# Integrated_LED.net
KiCad netlist of a schematic drawn in Altium Designer
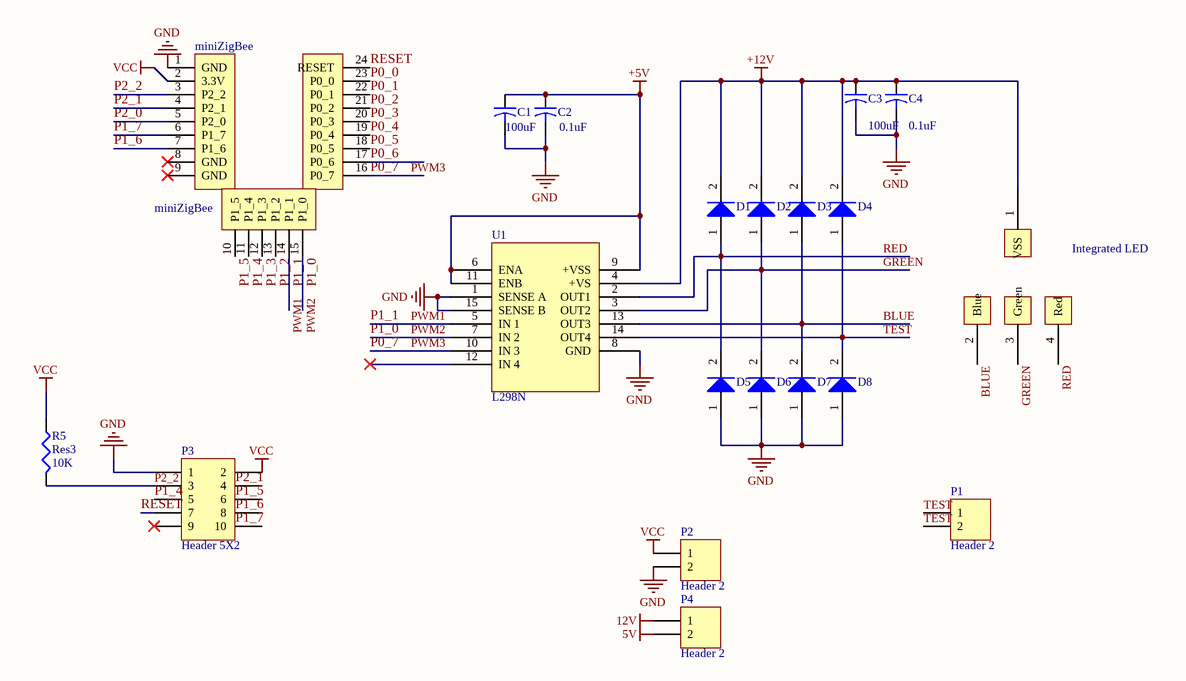
[diagram p0: Integrated LED.SCHDOC]

(export (version "E")
  (design (tool "Eeschema 10.0.6"))
  (components
    (comp (ref "C1")
      (value "100uF")
      (footprint "PCBComponent_1")
      (description "Capacitor")
      (fields (field (name "PUBLISHER") "Altium Limited"))
      (libsource (lib "Miscellaneous Devices") (part "Cap2"))
    )
    (comp (ref "C2")
      (value "0.1uF")
      (footprint "PCBComponent_1")
      (description "Capacitor")
      (fields (field (name "PUBLISHER") "Altium Limited"))
      (libsource (lib "Miscellaneous Devices") (part "Cap2"))
    )
    (comp (ref "C3")
      (value "100uF")
      (footprint "PCBComponent_1")
      (description "Capacitor")
      (fields (field (name "PUBLISHER") "Altium Limited"))
      (libsource (lib "Miscellaneous Devices") (part "Cap2"))
    )
    (comp (ref "C4")
      (value "0.1uF")
      (footprint "PCBComponent_1")
      (description "Capacitor")
      (fields (field (name "PUBLISHER") "Altium Limited"))
      (libsource (lib "Miscellaneous Devices") (part "Cap2"))
    )
    (comp (ref "D1")
      (value "IN4007")
      (footprint "IN4007")
      (libsource (lib "my Integrated lib ") (part "IN4007"))
    )
    (comp (ref "D2")
      (value "IN4007")
      (footprint "IN4007")
      (libsource (lib "my Integrated lib ") (part "IN4007"))
    )
    (comp (ref "D3")
      (value "IN4007")
      (footprint "IN4007")
      (libsource (lib "my Integrated lib ") (part "IN4007"))
    )
    (comp (ref "D4")
      (value "IN4007")
      (footprint "IN4007")
      (libsource (lib "my Integrated lib ") (part "IN4007"))
    )
    (comp (ref "D5")
      (value "IN4007")
      (footprint "IN4007")
      (libsource (lib "my Integrated lib ") (part "IN4007"))
    )
    (comp (ref "D6")
      (value "IN4007")
      (footprint "IN4007")
      (libsource (lib "my Integrated lib ") (part "IN4007"))
    )
    (comp (ref "D7")
      (value "IN4007")
      (footprint "IN4007")
      (libsource (lib "my Integrated lib ") (part "IN4007"))
    )
    (comp (ref "D8")
      (value "IN4007")
      (footprint "IN4007")
      (libsource (lib "my Integrated lib ") (part "IN4007"))
    )
    (comp (ref "Integrated LED")
      (value "Integrated LED")
      (footprint "Integrated LED")
      (libsource (lib "my Integrated lib ") (part "Integrated LED"))
    )
    (comp (ref "miniZigBee")
      (value "miniZigBee")
      (footprint "miniZigBee")
      (libsource (lib "my Integrated lib ") (part "miniZigBee"))
    )
    (comp (ref "P1")
      (value "Header 2")
      (footprint "HDR1X2")
      (description "Header, 2-Pin")
      (fields (field (name "PUBLISHER") "Altium Limited"))
      (libsource (lib "Miscellaneous Connectors") (part "Header 2"))
    )
    (comp (ref "P2")
      (value "Header 2")
      (footprint "HDR1X2")
      (description "Header, 2-Pin")
      (fields (field (name "PUBLISHER") "Altium Limited"))
      (libsource (lib "Miscellaneous Connectors") (part "Header 2"))
    )
    (comp (ref "P3")
      (value "Header 5X2")
      (footprint "HDR2X5")
      (description "Header, 5-Pin, Dual row")
      (fields (field (name "PUBLISHER") "Altium Limited"))
      (libsource (lib "Miscellaneous Connectors") (part "Header 5X2"))
    )
    (comp (ref "P4")
      (value "Header 2")
      (footprint "HDR1X2")
      (description "Header, 2-Pin")
      (fields (field (name "PUBLISHER") "Altium Limited"))
      (libsource (lib "Miscellaneous Connectors") (part "Header 2"))
    )
    (comp (ref "R5")
      (value "Res3")
      (footprint "J1-0603")
      (description "Resistor")
      (fields (field (name "ALTIUM_VALUE") "10K") (field (name "PUBLISHER") "Altium Limited"))
      (libsource (lib "Miscellaneous Devices") (part "Res3"))
    )
    (comp (ref "U1") (value "L298N") (footprint "L298N - duplicate") (libsource (lib "KU1") (part "L298N")))
  )
  (nets
    (net (code "1") (name "+5V") (class "Default")
      (node (ref "C1") (pin "1") (pinfunction "1_1") (pintype "passive"))
      (node (ref "C2") (pin "1") (pinfunction "1_1") (pintype "passive"))
      (node (ref "U1") (pin "11") (pinfunction "ENB_11") (pintype "passive"))
      (node (ref "U1") (pin "6") (pinfunction "ENA_6") (pintype "passive"))
      (node (ref "U1") (pin "9") (pinfunction "+VSS_9") (pintype "passive"))
    )
    (net (code "2") (name "+12V") (class "Default")
      (node (ref "C3") (pin "1") (pinfunction "1_1") (pintype "passive"))
      (node (ref "C4") (pin "1") (pinfunction "1_1") (pintype "passive"))
      (node (ref "D1") (pin "2") (pinfunction "K_2") (pintype "passive"))
      (node (ref "D2") (pin "2") (pinfunction "K_2") (pintype "passive"))
      (node (ref "D3") (pin "2") (pinfunction "K_2") (pintype "passive"))
      (node (ref "D4") (pin "2") (pinfunction "K_2") (pintype "passive"))
      (node (ref "Integrated LED") (pin "1") (pinfunction "VSS_1") (pintype "passive"))
      (node (ref "U1") (pin "4") (pinfunction "+VS_4") (pintype "passive"))
    )
    (net (code "3") (name "/BLUE") (class "Default")
      (node (ref "D3") (pin "1") (pinfunction "A_1") (pintype "passive"))
      (node (ref "D7") (pin "2") (pinfunction "K_2") (pintype "passive"))
      (node (ref "Integrated LED") (pin "2") (pinfunction "Blue_2") (pintype "passive"))
      (node (ref "U1") (pin "13") (pinfunction "OUT3_13") (pintype "passive"))
    )
    (net (code "4") (name "/GREEN") (class "Default")
      (node (ref "D2") (pin "1") (pinfunction "A_1") (pintype "passive"))
      (node (ref "D6") (pin "2") (pinfunction "K_2") (pintype "passive"))
      (node (ref "Integrated LED") (pin "3") (pinfunction "Green_3") (pintype "passive"))
      (node (ref "U1") (pin "3") (pinfunction "OUT2_3") (pintype "passive"))
    )
    (net (code "5") (name "/P0_0") (class "Default")
      (node (ref "miniZigBee") (pin "23") (pinfunction "P0_0_23") (pintype "passive"))
    )
    (net (code "6") (name "/P0_1") (class "Default")
      (node (ref "miniZigBee") (pin "22") (pinfunction "P0_1_22") (pintype "passive"))
    )
    (net (code "7") (name "/P0_2") (class "Default")
      (node (ref "miniZigBee") (pin "21") (pinfunction "P0_2_21") (pintype "passive"))
    )
    (net (code "8") (name "/P0_3") (class "Default")
      (node (ref "miniZigBee") (pin "20") (pinfunction "P0_3_20") (pintype "passive"))
    )
    (net (code "9") (name "/P0_4") (class "Default")
      (node (ref "miniZigBee") (pin "19") (pinfunction "P0_4_19") (pintype "passive"))
    )
    (net (code "10") (name "/P0_5") (class "Default")
      (node (ref "miniZigBee") (pin "18") (pinfunction "P0_5_18") (pintype "passive"))
    )
    (net (code "11") (name "/P0_6") (class "Default")
      (node (ref "miniZigBee") (pin "17") (pinfunction "P0_6_17") (pintype "passive"))
    )
    (net (code "12") (name "/P0_7") (class "Default")
      (node (ref "U1") (pin "10") (pinfunction "IN_3_10") (pintype "passive"))
      (node (ref "miniZigBee") (pin "16") (pinfunction "P0_7_16") (pintype "passive"))
    )
    (net (code "13") (name "/P1_0") (class "Default")
      (node (ref "U1") (pin "7") (pinfunction "IN_2_7") (pintype "passive"))
      (node (ref "miniZigBee") (pin "15") (pinfunction "P1_0_15") (pintype "passive"))
    )
    (net (code "14") (name "/P1_1") (class "Default")
      (node (ref "U1") (pin "5") (pinfunction "IN_1_5") (pintype "passive"))
      (node (ref "miniZigBee") (pin "14") (pinfunction "P1_1_14") (pintype "passive"))
    )
    (net (code "15") (name "/P1_2") (class "Default")
      (node (ref "miniZigBee") (pin "13") (pinfunction "P1_2_13") (pintype "passive"))
    )
    (net (code "16") (name "/P1_3") (class "Default")
      (node (ref "miniZigBee") (pin "12") (pinfunction "P1_3_12") (pintype "passive"))
    )
    (net (code "17") (name "/P1_4") (class "Default")
      (node (ref "P3") (pin "5") (pinfunction "5_5") (pintype "passive"))
      (node (ref "miniZigBee") (pin "11") (pinfunction "P1_4_11") (pintype "passive"))
    )
    (net (code "18") (name "/P1_5") (class "Default")
      (node (ref "miniZigBee") (pin "10") (pinfunction "P1_5_10") (pintype "passive"))
    )
    (net (code "19") (name "/P1_6") (class "Default")
      (node (ref "miniZigBee") (pin "7") (pinfunction "P1_6_7") (pintype "passive"))
    )
    (net (code "20") (name "/P1_7") (class "Default")
      (node (ref "miniZigBee") (pin "6") (pinfunction "P1_7_6") (pintype "passive"))
    )
    (net (code "21") (name "/P2_0") (class "Default")
      (node (ref "miniZigBee") (pin "5") (pinfunction "P2_0_5") (pintype "passive"))
    )
    (net (code "22") (name "/P2_1") (class "Default")
      (node (ref "miniZigBee") (pin "4") (pinfunction "P2_1_4") (pintype "passive"))
    )
    (net (code "23") (name "/P2_2") (class "Default")
      (node (ref "P3") (pin "3") (pinfunction "3_3") (pintype "passive"))
      (node (ref "R5") (pin "2") (pinfunction "2_2") (pintype "passive"))
      (node (ref "miniZigBee") (pin "3") (pinfunction "P2_2_3") (pintype "passive"))
    )
    (net (code "24") (name "/RED") (class "Default")
      (node (ref "D1") (pin "1") (pinfunction "A_1") (pintype "passive"))
      (node (ref "D5") (pin "2") (pinfunction "K_2") (pintype "passive"))
      (node (ref "Integrated LED") (pin "4") (pinfunction "Red_4") (pintype "passive"))
      (node (ref "U1") (pin "2") (pinfunction "OUT1_2") (pintype "passive"))
    )
    (net (code "25") (name "/RESET") (class "Default")
      (node (ref "P3") (pin "7") (pinfunction "7_7") (pintype "passive"))
      (node (ref "miniZigBee") (pin "24") (pinfunction "RESET_24") (pintype "passive"))
    )
    (net (code "26") (name "/TEST") (class "Default")
      (node (ref "D4") (pin "1") (pinfunction "A_1") (pintype "passive"))
      (node (ref "D8") (pin "2") (pinfunction "K_2") (pintype "passive"))
      (node (ref "P1") (pin "1") (pinfunction "1_1") (pintype "passive"))
      (node (ref "P1") (pin "2") (pinfunction "2_2") (pintype "passive"))
      (node (ref "U1") (pin "14") (pinfunction "OUT4_14") (pintype "passive"))
    )
    (net (code "27") (name "5V") (class "Default")
      (node (ref "P4") (pin "2") (pinfunction "2_2") (pintype "passive"))
    )
    (net (code "28") (name "12V") (class "Default")
      (node (ref "P4") (pin "1") (pinfunction "1_1") (pintype "passive"))
    )
    (net (code "29") (name "GND") (class "Default")
      (node (ref "C1") (pin "2") (pinfunction "2_2") (pintype "passive"))
      (node (ref "C2") (pin "2") (pinfunction "2_2") (pintype "passive"))
      (node (ref "C3") (pin "2") (pinfunction "2_2") (pintype "passive"))
      (node (ref "C4") (pin "2") (pinfunction "2_2") (pintype "passive"))
      (node (ref "D5") (pin "1") (pinfunction "A_1") (pintype "passive"))
      (node (ref "D6") (pin "1") (pinfunction "A_1") (pintype "passive"))
      (node (ref "D7") (pin "1") (pinfunction "A_1") (pintype "passive"))
      (node (ref "D8") (pin "1") (pinfunction "A_1") (pintype "passive"))
      (node (ref "P2") (pin "2") (pinfunction "2_2") (pintype "passive"))
      (node (ref "P3") (pin "1") (pinfunction "1_1") (pintype "passive"))
      (node (ref "U1") (pin "1") (pinfunction "SENSE_A_1") (pintype "passive"))
      (node (ref "U1") (pin "15") (pinfunction "SENSE_B_15") (pintype "passive"))
      (node (ref "U1") (pin "8") (pinfunction "GND_8") (pintype "passive"))
      (node (ref "miniZigBee") (pin "1") (pinfunction "GND_1") (pintype "passive"))
    )
    (net (code "30") (name "VCC") (class "Default")
      (node (ref "P2") (pin "1") (pinfunction "1_1") (pintype "passive"))
      (node (ref "P3") (pin "2") (pinfunction "2_2") (pintype "passive"))
      (node (ref "R5") (pin "1") (pinfunction "1_1") (pintype "passive"))
      (node (ref "miniZigBee") (pin "2") (pinfunction "3.3V_2") (pintype "passive"))
    )
    (net (code "31") (name "unconnected-(P3-Pad4)") (class "Default")
      (node (ref "P3") (pin "4") (pinfunction "4_4") (pintype "passive"))
    )
    (net (code "32") (name "unconnected-(P3-Pad6)") (class "Default")
      (node (ref "P3") (pin "6") (pinfunction "6_6") (pintype "passive"))
    )
    (net (code "33") (name "unconnected-(P3-Pad8)") (class "Default")
      (node (ref "P3") (pin "8") (pinfunction "8_8") (pintype "passive"))
    )
    (net (code "34") (name "unconnected-(P3-Pad9)") (class "Default")
      (node (ref "P3") (pin "9") (pinfunction "9_9") (pintype "passive+no_connect"))
    )
    (net (code "35") (name "unconnected-(P3-Pad10)") (class "Default")
      (node (ref "P3") (pin "10") (pinfunction "10_10") (pintype "passive"))
    )
    (net (code "36") (name "unconnected-(U1-IN_4-Pad12)") (class "Default")
      (node (ref "U1") (pin "12") (pinfunction "IN_4_12") (pintype "passive+no_connect"))
    )
    (net (code "37") (name "unconnected-(miniZigBee-GND-Pad8)") (class "Default")
      (node (ref "miniZigBee") (pin "8") (pinfunction "GND_8") (pintype "passive+no_connect"))
    )
    (net (code "38") (name "unconnected-(miniZigBee-GND-Pad9)") (class "Default")
      (node (ref "miniZigBee") (pin "9") (pinfunction "GND_9") (pintype "passive+no_connect"))
    )
  )
)
